# AnalogIn.net
KiCad netlist of a schematic drawn in Altium Designer
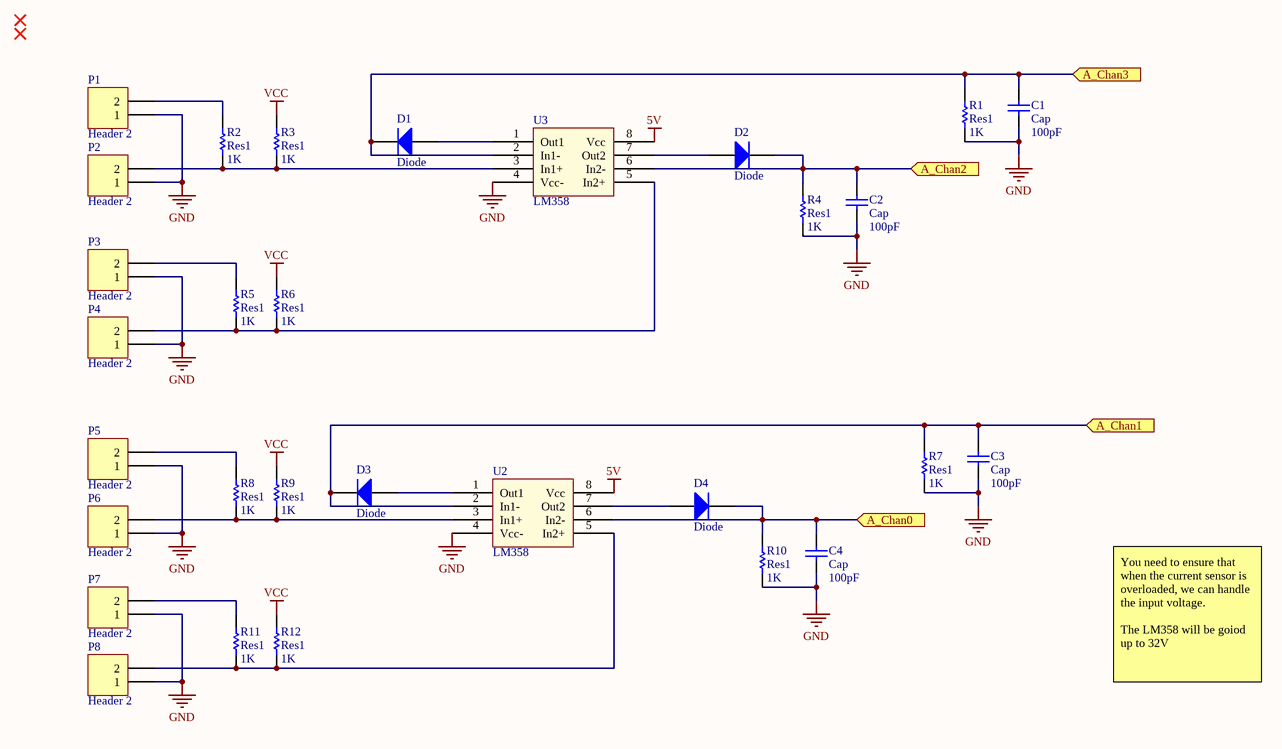
[diagram p0: AnalogIn.SchDoc]

(export (version "E")
  (design (tool "Eeschema 10.0.6"))
  (components
    (comp (ref "C1")
      (value "Cap")
      (footprint "CAPC2012X04M")
      (description "Capacitor")
      (fields (field (name "ALTIUM_VALUE") "100pF") (field (name "PUBLISHER") "Altium Limited"))
      (libsource (lib "Miscellaneous Devices") (part "Cap"))
    )
    (comp (ref "C2")
      (value "Cap")
      (footprint "CAPC2012X04M")
      (description "Capacitor")
      (fields (field (name "ALTIUM_VALUE") "100pF") (field (name "PUBLISHER") "Altium Limited"))
      (libsource (lib "Miscellaneous Devices") (part "Cap"))
    )
    (comp (ref "C3")
      (value "Cap")
      (footprint "CAPC2012X04M")
      (description "Capacitor")
      (fields (field (name "ALTIUM_VALUE") "100pF") (field (name "PUBLISHER") "Altium Limited"))
      (libsource (lib "Miscellaneous Devices") (part "Cap"))
    )
    (comp (ref "C4")
      (value "Cap")
      (footprint "CAPC2012X04M")
      (description "Capacitor")
      (fields (field (name "ALTIUM_VALUE") "100pF") (field (name "PUBLISHER") "Altium Limited"))
      (libsource (lib "Miscellaneous Devices") (part "Cap"))
    )
    (comp (ref "D1")
      (value "Diode")
      (footprint "DIOC2012X04M")
      (description "Default Diode")
      (fields (field (name "PUBLISHER") "Altium Limited"))
      (libsource (lib "Miscellaneous Devices") (part "Diode"))
    )
    (comp (ref "D2")
      (value "Diode")
      (footprint "DIOC2012X04M")
      (description "Default Diode")
      (fields (field (name "PUBLISHER") "Altium Limited"))
      (libsource (lib "Miscellaneous Devices") (part "Diode"))
    )
    (comp (ref "D3")
      (value "Diode")
      (footprint "DIOC2012X04M")
      (description "Default Diode")
      (fields (field (name "PUBLISHER") "Altium Limited"))
      (libsource (lib "Miscellaneous Devices") (part "Diode"))
    )
    (comp (ref "D4")
      (value "Diode")
      (footprint "DIOC2012X04M")
      (description "Default Diode")
      (fields (field (name "PUBLISHER") "Altium Limited"))
      (libsource (lib "Miscellaneous Devices") (part "Diode"))
    )
    (comp (ref "P1")
      (value "Header 2")
      (footprint "HDR1X2")
      (description "Header, 2-Pin")
      (fields (field (name "PUBLISHER") "Altium Limited"))
      (libsource (lib "Miscellaneous Connectors") (part "Header 2"))
    )
    (comp (ref "P2")
      (value "Header 2")
      (footprint "WURTH- WR-TBL 2pin 5mmpitch")
      (description "Header, 2-Pin")
      (fields (field (name "PUBLISHER") "Altium Limited"))
      (libsource (lib "Miscellaneous Connectors") (part "Header 2"))
    )
    (comp (ref "P3")
      (value "Header 2")
      (footprint "HDR1X2")
      (description "Header, 2-Pin")
      (fields (field (name "PUBLISHER") "Altium Limited"))
      (libsource (lib "Miscellaneous Connectors") (part "Header 2"))
    )
    (comp (ref "P4")
      (value "Header 2")
      (footprint "WURTH- WR-TBL 2pin 5mmpitch")
      (description "Header, 2-Pin")
      (fields (field (name "PUBLISHER") "Altium Limited"))
      (libsource (lib "Miscellaneous Connectors") (part "Header 2"))
    )
    (comp (ref "P5")
      (value "Header 2")
      (footprint "HDR1X2")
      (description "Header, 2-Pin")
      (fields (field (name "PUBLISHER") "Altium Limited"))
      (libsource (lib "Miscellaneous Connectors") (part "Header 2"))
    )
    (comp (ref "P6")
      (value "Header 2")
      (footprint "WURTH- WR-TBL 2pin 5mmpitch")
      (description "Header, 2-Pin")
      (fields (field (name "PUBLISHER") "Altium Limited"))
      (libsource (lib "Miscellaneous Connectors") (part "Header 2"))
    )
    (comp (ref "P7")
      (value "Header 2")
      (footprint "HDR1X2")
      (description "Header, 2-Pin")
      (fields (field (name "PUBLISHER") "Altium Limited"))
      (libsource (lib "Miscellaneous Connectors") (part "Header 2"))
    )
    (comp (ref "P8")
      (value "Header 2")
      (footprint "WURTH- WR-TBL 2pin 5mmpitch")
      (description "Header, 2-Pin")
      (fields (field (name "PUBLISHER") "Altium Limited"))
      (libsource (lib "Miscellaneous Connectors") (part "Header 2"))
    )
    (comp (ref "R1")
      (value "Res1")
      (footprint "RESC2012X04M")
      (description "Resistor")
      (fields (field (name "ALTIUM_VALUE") "1K") (field (name "PUBLISHER") "Altium Limited"))
      (libsource (lib "Miscellaneous Devices") (part "Res1"))
    )
    (comp (ref "R2")
      (value "Res1")
      (footprint "RESC2012X04M")
      (description "Resistor")
      (fields (field (name "ALTIUM_VALUE") "1K") (field (name "PUBLISHER") "Altium Limited"))
      (libsource (lib "Miscellaneous Devices") (part "Res1"))
    )
    (comp (ref "R3")
      (value "Res1")
      (footprint "RESC2012X04M")
      (description "Resistor")
      (fields (field (name "ALTIUM_VALUE") "1K") (field (name "PUBLISHER") "Altium Limited"))
      (libsource (lib "Miscellaneous Devices") (part "Res1"))
    )
    (comp (ref "R4")
      (value "Res1")
      (footprint "RESC2012X04M")
      (description "Resistor")
      (fields (field (name "ALTIUM_VALUE") "1K") (field (name "PUBLISHER") "Altium Limited"))
      (libsource (lib "Miscellaneous Devices") (part "Res1"))
    )
    (comp (ref "R5")
      (value "Res1")
      (footprint "RESC2012X04M")
      (description "Resistor")
      (fields (field (name "ALTIUM_VALUE") "1K") (field (name "PUBLISHER") "Altium Limited"))
      (libsource (lib "Miscellaneous Devices") (part "Res1"))
    )
    (comp (ref "R6")
      (value "Res1")
      (footprint "RESC2012X04M")
      (description "Resistor")
      (fields (field (name "ALTIUM_VALUE") "1K") (field (name "PUBLISHER") "Altium Limited"))
      (libsource (lib "Miscellaneous Devices") (part "Res1"))
    )
    (comp (ref "R7")
      (value "Res1")
      (footprint "RESC2012X04M")
      (description "Resistor")
      (fields (field (name "ALTIUM_VALUE") "1K") (field (name "PUBLISHER") "Altium Limited"))
      (libsource (lib "Miscellaneous Devices") (part "Res1"))
    )
    (comp (ref "R8")
      (value "Res1")
      (footprint "RESC2012X04M")
      (description "Resistor")
      (fields (field (name "ALTIUM_VALUE") "1K") (field (name "PUBLISHER") "Altium Limited"))
      (libsource (lib "Miscellaneous Devices") (part "Res1"))
    )
    (comp (ref "R9")
      (value "Res1")
      (footprint "RESC2012X04M")
      (description "Resistor")
      (fields (field (name "ALTIUM_VALUE") "1K") (field (name "PUBLISHER") "Altium Limited"))
      (libsource (lib "Miscellaneous Devices") (part "Res1"))
    )
    (comp (ref "R10")
      (value "Res1")
      (footprint "RESC2012X04M")
      (description "Resistor")
      (fields (field (name "ALTIUM_VALUE") "1K") (field (name "PUBLISHER") "Altium Limited"))
      (libsource (lib "Miscellaneous Devices") (part "Res1"))
    )
    (comp (ref "R11")
      (value "Res1")
      (footprint "RESC2012X04M")
      (description "Resistor")
      (fields (field (name "ALTIUM_VALUE") "1K") (field (name "PUBLISHER") "Altium Limited"))
      (libsource (lib "Miscellaneous Devices") (part "Res1"))
    )
    (comp (ref "R12")
      (value "Res1")
      (footprint "RESC2012X04M")
      (description "Resistor")
      (fields (field (name "ALTIUM_VALUE") "1K") (field (name "PUBLISHER") "Altium Limited"))
      (libsource (lib "Miscellaneous Devices") (part "Res1"))
    )
    (comp (ref "U2")
      (value "LM358")
      (footprint "SOIC127P600X155-8N")
      (libsource (lib "Parts") (part "LM358"))
    )
    (comp (ref "U3")
      (value "LM358")
      (footprint "SOIC127P600X155-8N")
      (libsource (lib "Parts") (part "LM358"))
    )
  )
  (nets
    (net (code "1") (name "/A_Chan0") (class "Default")
      (node (ref "C4") (pin "2") (pinfunction "2_2") (pintype "passive"))
      (node (ref "D4") (pin "2") (pinfunction "K_2") (pintype "passive"))
      (node (ref "R10") (pin "2") (pinfunction "2_2") (pintype "passive"))
      (node (ref "U2") (pin "6") (pinfunction "In2-_6") (pintype "passive"))
    )
    (net (code "2") (name "/A_Chan1") (class "Default")
      (node (ref "C3") (pin "2") (pinfunction "2_2") (pintype "passive"))
      (node (ref "D3") (pin "2") (pinfunction "K_2") (pintype "passive"))
      (node (ref "R7") (pin "2") (pinfunction "2_2") (pintype "passive"))
      (node (ref "U2") (pin "2") (pinfunction "In1-_2") (pintype "passive"))
    )
    (net (code "3") (name "/A_Chan2") (class "Default")
      (node (ref "C2") (pin "2") (pinfunction "2_2") (pintype "passive"))
      (node (ref "D2") (pin "2") (pinfunction "K_2") (pintype "passive"))
      (node (ref "R4") (pin "2") (pinfunction "2_2") (pintype "passive"))
      (node (ref "U3") (pin "6") (pinfunction "In2-_6") (pintype "passive"))
    )
    (net (code "4") (name "/A_Chan3") (class "Default")
      (node (ref "C1") (pin "2") (pinfunction "2_2") (pintype "passive"))
      (node (ref "D1") (pin "2") (pinfunction "K_2") (pintype "passive"))
      (node (ref "R1") (pin "2") (pinfunction "2_2") (pintype "passive"))
      (node (ref "U3") (pin "2") (pinfunction "In1-_2") (pintype "passive"))
    )
    (net (code "5") (name "5V") (class "Default")
      (node (ref "U2") (pin "8") (pinfunction "Vcc_8") (pintype "passive"))
      (node (ref "U3") (pin "8") (pinfunction "Vcc_8") (pintype "passive"))
    )
    (net (code "6") (name "GND") (class "Default")
      (node (ref "C1") (pin "1") (pinfunction "1_1") (pintype "passive"))
      (node (ref "C2") (pin "1") (pinfunction "1_1") (pintype "passive"))
      (node (ref "C3") (pin "1") (pinfunction "1_1") (pintype "passive"))
      (node (ref "C4") (pin "1") (pinfunction "1_1") (pintype "passive"))
      (node (ref "P1") (pin "1") (pinfunction "1_1") (pintype "passive"))
      (node (ref "P2") (pin "1") (pinfunction "1_1") (pintype "passive"))
      (node (ref "P3") (pin "1") (pinfunction "1_1") (pintype "passive"))
      (node (ref "P4") (pin "1") (pinfunction "1_1") (pintype "passive"))
      (node (ref "P5") (pin "1") (pinfunction "1_1") (pintype "passive"))
      (node (ref "P6") (pin "1") (pinfunction "1_1") (pintype "passive"))
      (node (ref "P7") (pin "1") (pinfunction "1_1") (pintype "passive"))
      (node (ref "P8") (pin "1") (pinfunction "1_1") (pintype "passive"))
      (node (ref "R1") (pin "1") (pinfunction "1_1") (pintype "passive"))
      (node (ref "R10") (pin "1") (pinfunction "1_1") (pintype "passive"))
      (node (ref "R4") (pin "1") (pinfunction "1_1") (pintype "passive"))
      (node (ref "R7") (pin "1") (pinfunction "1_1") (pintype "passive"))
      (node (ref "U2") (pin "4") (pinfunction "Vcc-_4") (pintype "passive"))
      (node (ref "U3") (pin "4") (pinfunction "Vcc-_4") (pintype "passive"))
    )
    (net (code "7") (name "Net-(D1-A)") (class "Default")
      (node (ref "D1") (pin "1") (pinfunction "A_1") (pintype "passive"))
      (node (ref "U3") (pin "1") (pinfunction "Out1_1") (pintype "passive"))
    )
    (net (code "8") (name "Net-(D2-A)") (class "Default")
      (node (ref "D2") (pin "1") (pinfunction "A_1") (pintype "passive"))
      (node (ref "U3") (pin "7") (pinfunction "Out2_7") (pintype "passive"))
    )
    (net (code "9") (name "Net-(D3-A)") (class "Default")
      (node (ref "D3") (pin "1") (pinfunction "A_1") (pintype "passive"))
      (node (ref "U2") (pin "1") (pinfunction "Out1_1") (pintype "passive"))
    )
    (net (code "10") (name "Net-(D4-A)") (class "Default")
      (node (ref "D4") (pin "1") (pinfunction "A_1") (pintype "passive"))
      (node (ref "U2") (pin "7") (pinfunction "Out2_7") (pintype "passive"))
    )
    (net (code "11") (name "Net-(P1-Pad2)") (class "Default")
      (node (ref "P1") (pin "2") (pinfunction "2_2") (pintype "passive"))
      (node (ref "R2") (pin "1") (pinfunction "1_1") (pintype "passive"))
    )
    (net (code "12") (name "Net-(P3-Pad2)") (class "Default")
      (node (ref "P3") (pin "2") (pinfunction "2_2") (pintype "passive"))
      (node (ref "R5") (pin "1") (pinfunction "1_1") (pintype "passive"))
    )
    (net (code "13") (name "Net-(P5-Pad2)") (class "Default")
      (node (ref "P5") (pin "2") (pinfunction "2_2") (pintype "passive"))
      (node (ref "R8") (pin "1") (pinfunction "1_1") (pintype "passive"))
    )
    (net (code "14") (name "Net-(P7-Pad2)") (class "Default")
      (node (ref "P7") (pin "2") (pinfunction "2_2") (pintype "passive"))
      (node (ref "R11") (pin "1") (pinfunction "1_1") (pintype "passive"))
    )
    (net (code "15") (name "Net-(U2-In1+)") (class "Default")
      (node (ref "P6") (pin "2") (pinfunction "2_2") (pintype "passive"))
      (node (ref "R8") (pin "2") (pinfunction "2_2") (pintype "passive"))
      (node (ref "R9") (pin "2") (pinfunction "2_2") (pintype "passive"))
      (node (ref "U2") (pin "3") (pinfunction "In1+_3") (pintype "passive"))
    )
    (net (code "16") (name "Net-(U2-In2+)") (class "Default")
      (node (ref "P8") (pin "2") (pinfunction "2_2") (pintype "passive"))
      (node (ref "R11") (pin "2") (pinfunction "2_2") (pintype "passive"))
      (node (ref "R12") (pin "2") (pinfunction "2_2") (pintype "passive"))
      (node (ref "U2") (pin "5") (pinfunction "In2+_5") (pintype "passive"))
    )
    (net (code "17") (name "Net-(U3-In1+)") (class "Default")
      (node (ref "P2") (pin "2") (pinfunction "2_2") (pintype "passive"))
      (node (ref "R2") (pin "2") (pinfunction "2_2") (pintype "passive"))
      (node (ref "R3") (pin "2") (pinfunction "2_2") (pintype "passive"))
      (node (ref "U3") (pin "3") (pinfunction "In1+_3") (pintype "passive"))
    )
    (net (code "18") (name "Net-(U3-In2+)") (class "Default")
      (node (ref "P4") (pin "2") (pinfunction "2_2") (pintype "passive"))
      (node (ref "R5") (pin "2") (pinfunction "2_2") (pintype "passive"))
      (node (ref "R6") (pin "2") (pinfunction "2_2") (pintype "passive"))
      (node (ref "U3") (pin "5") (pinfunction "In2+_5") (pintype "passive"))
    )
    (net (code "19") (name "VCC") (class "Default")
      (node (ref "R12") (pin "1") (pinfunction "1_1") (pintype "passive"))
      (node (ref "R3") (pin "1") (pinfunction "1_1") (pintype "passive"))
      (node (ref "R6") (pin "1") (pinfunction "1_1") (pintype "passive"))
      (node (ref "R9") (pin "1") (pinfunction "1_1") (pintype "passive"))
    )
  )
)
